# schema.net
KiCad netlist of a schematic drawn in EAGLE
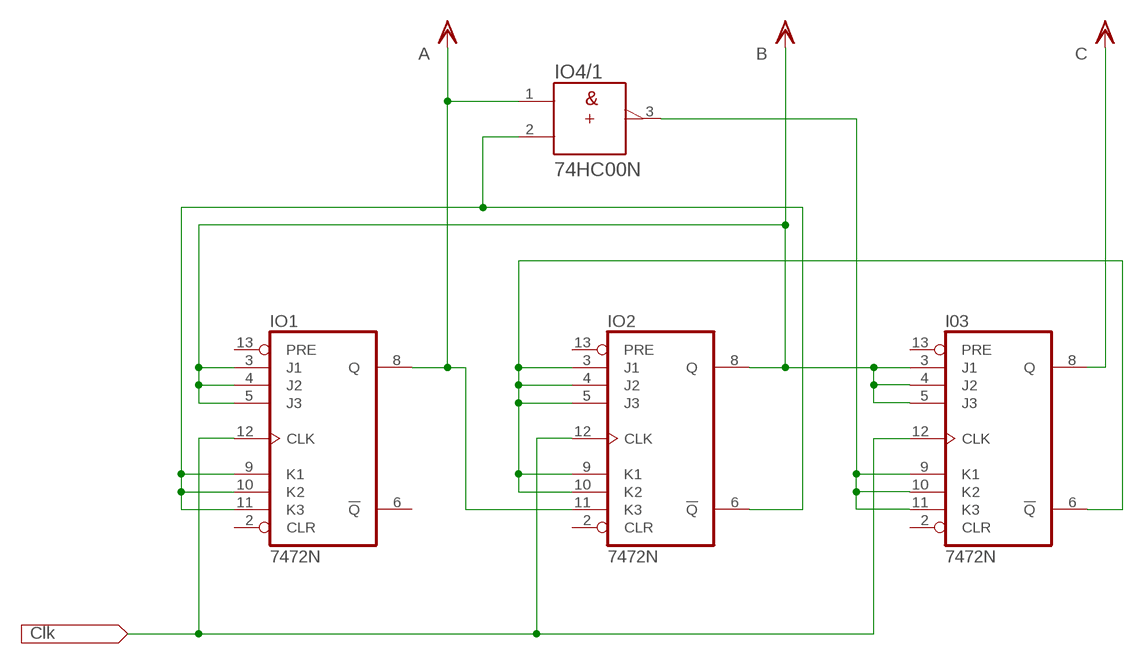
[diagram p0: schematic, sheet 1]

(export (version "E")
  (design (tool "Eeschema 10.0.6"))
  (components
    (comp (ref "I03")
      (value "7472N")
      (footprint "eagle-import:DIL14")
      (libsource (lib "eagle-import") (part "7472N"))
    )
    (comp (ref "IO1")
      (value "7472N")
      (footprint "eagle-import:DIL14")
      (libsource (lib "eagle-import") (part "7472N"))
    )
    (comp (ref "IO2")
      (value "7472N")
      (footprint "eagle-import:DIL14")
      (libsource (lib "eagle-import") (part "7472N"))
    )
    (comp (ref "IO4")
      (value "74HC00N")
      (footprint "eagle-import:DIL14")
      (libsource (lib "eagle-import") (part "7400NHC"))
    )
  )
  (nets
    (net (code "1") (name "A") (class "Default")
      (node (ref "I03") (pin "3") (pinfunction "J1_3") (pintype "input"))
      (node (ref "I03") (pin "4") (pinfunction "J2_4") (pintype "input"))
      (node (ref "I03") (pin "5") (pinfunction "J3_5") (pintype "input"))
      (node (ref "I03") (pin "8") (pinfunction "Q_8") (pintype "output"))
      (node (ref "IO1") (pin "3") (pinfunction "J1_3") (pintype "input"))
      (node (ref "IO1") (pin "4") (pinfunction "J2_4") (pintype "input"))
      (node (ref "IO1") (pin "5") (pinfunction "J3_5") (pintype "input"))
      (node (ref "IO1") (pin "8") (pinfunction "Q_8") (pintype "output"))
      (node (ref "IO2") (pin "11") (pinfunction "K3_11") (pintype "input"))
      (node (ref "IO2") (pin "8") (pinfunction "Q_8") (pintype "output"))
      (node (ref "IO4") (pin "1") (pinfunction "A_1") (pintype "input"))
    )
    (net (code "2") (name "Net-(I03A-CLK)") (class "Default")
      (node (ref "I03") (pin "12") (pinfunction "CLK_12") (pintype "input"))
      (node (ref "IO1") (pin "12") (pinfunction "CLK_12") (pintype "input"))
      (node (ref "IO2") (pin "12") (pinfunction "CLK_12") (pintype "input"))
    )
    (net (code "3") (name "Net-(I03A-K1)") (class "Default")
      (node (ref "I03") (pin "10") (pinfunction "K2_10") (pintype "input"))
      (node (ref "I03") (pin "11") (pinfunction "K3_11") (pintype "input"))
      (node (ref "I03") (pin "9") (pinfunction "K1_9") (pintype "input"))
      (node (ref "IO4") (pin "3") (pinfunction "Y_3") (pintype "output"))
    )
    (net (code "4") (name "Net-(I03A-~{Q})") (class "Default")
      (node (ref "I03") (pin "6") (pinfunction "~{Q}_6") (pintype "output"))
      (node (ref "IO2") (pin "10") (pinfunction "K2_10") (pintype "input"))
      (node (ref "IO2") (pin "3") (pinfunction "J1_3") (pintype "input"))
      (node (ref "IO2") (pin "4") (pinfunction "J2_4") (pintype "input"))
      (node (ref "IO2") (pin "5") (pinfunction "J3_5") (pintype "input"))
      (node (ref "IO2") (pin "9") (pinfunction "K1_9") (pintype "input"))
    )
    (net (code "5") (name "Net-(IO1A-K1)") (class "Default")
      (node (ref "IO1") (pin "10") (pinfunction "K2_10") (pintype "input"))
      (node (ref "IO1") (pin "11") (pinfunction "K3_11") (pintype "input"))
      (node (ref "IO1") (pin "9") (pinfunction "K1_9") (pintype "input"))
      (node (ref "IO2") (pin "6") (pinfunction "~{Q}_6") (pintype "output"))
      (node (ref "IO4") (pin "2") (pinfunction "B_2") (pintype "input"))
    )
    (net (code "6") (name "unconnected-(I03A-CLR-Pad2)") (class "Default")
      (node (ref "I03") (pin "2") (pinfunction "CLR_2") (pintype "input"))
    )
    (net (code "7") (name "unconnected-(I03A-PRE-Pad13)") (class "Default")
      (node (ref "I03") (pin "13") (pinfunction "PRE_13") (pintype "input"))
    )
    (net (code "8") (name "unconnected-(IO1A-CLR-Pad2)") (class "Default")
      (node (ref "IO1") (pin "2") (pinfunction "CLR_2") (pintype "input"))
    )
    (net (code "9") (name "unconnected-(IO1A-PRE-Pad13)") (class "Default")
      (node (ref "IO1") (pin "13") (pinfunction "PRE_13") (pintype "input"))
    )
    (net (code "10") (name "unconnected-(IO1A-~{Q}-Pad6)") (class "Default")
      (node (ref "IO1") (pin "6") (pinfunction "~{Q}_6") (pintype "output"))
    )
    (net (code "11") (name "unconnected-(IO2A-CLR-Pad2)") (class "Default")
      (node (ref "IO2") (pin "2") (pinfunction "CLR_2") (pintype "input"))
    )
    (net (code "12") (name "unconnected-(IO2A-PRE-Pad13)") (class "Default")
      (node (ref "IO2") (pin "13") (pinfunction "PRE_13") (pintype "input"))
    )
  )
)
